# VM3300_V0_1.net
KiCad netlist of a schematic drawn in Altium Designer
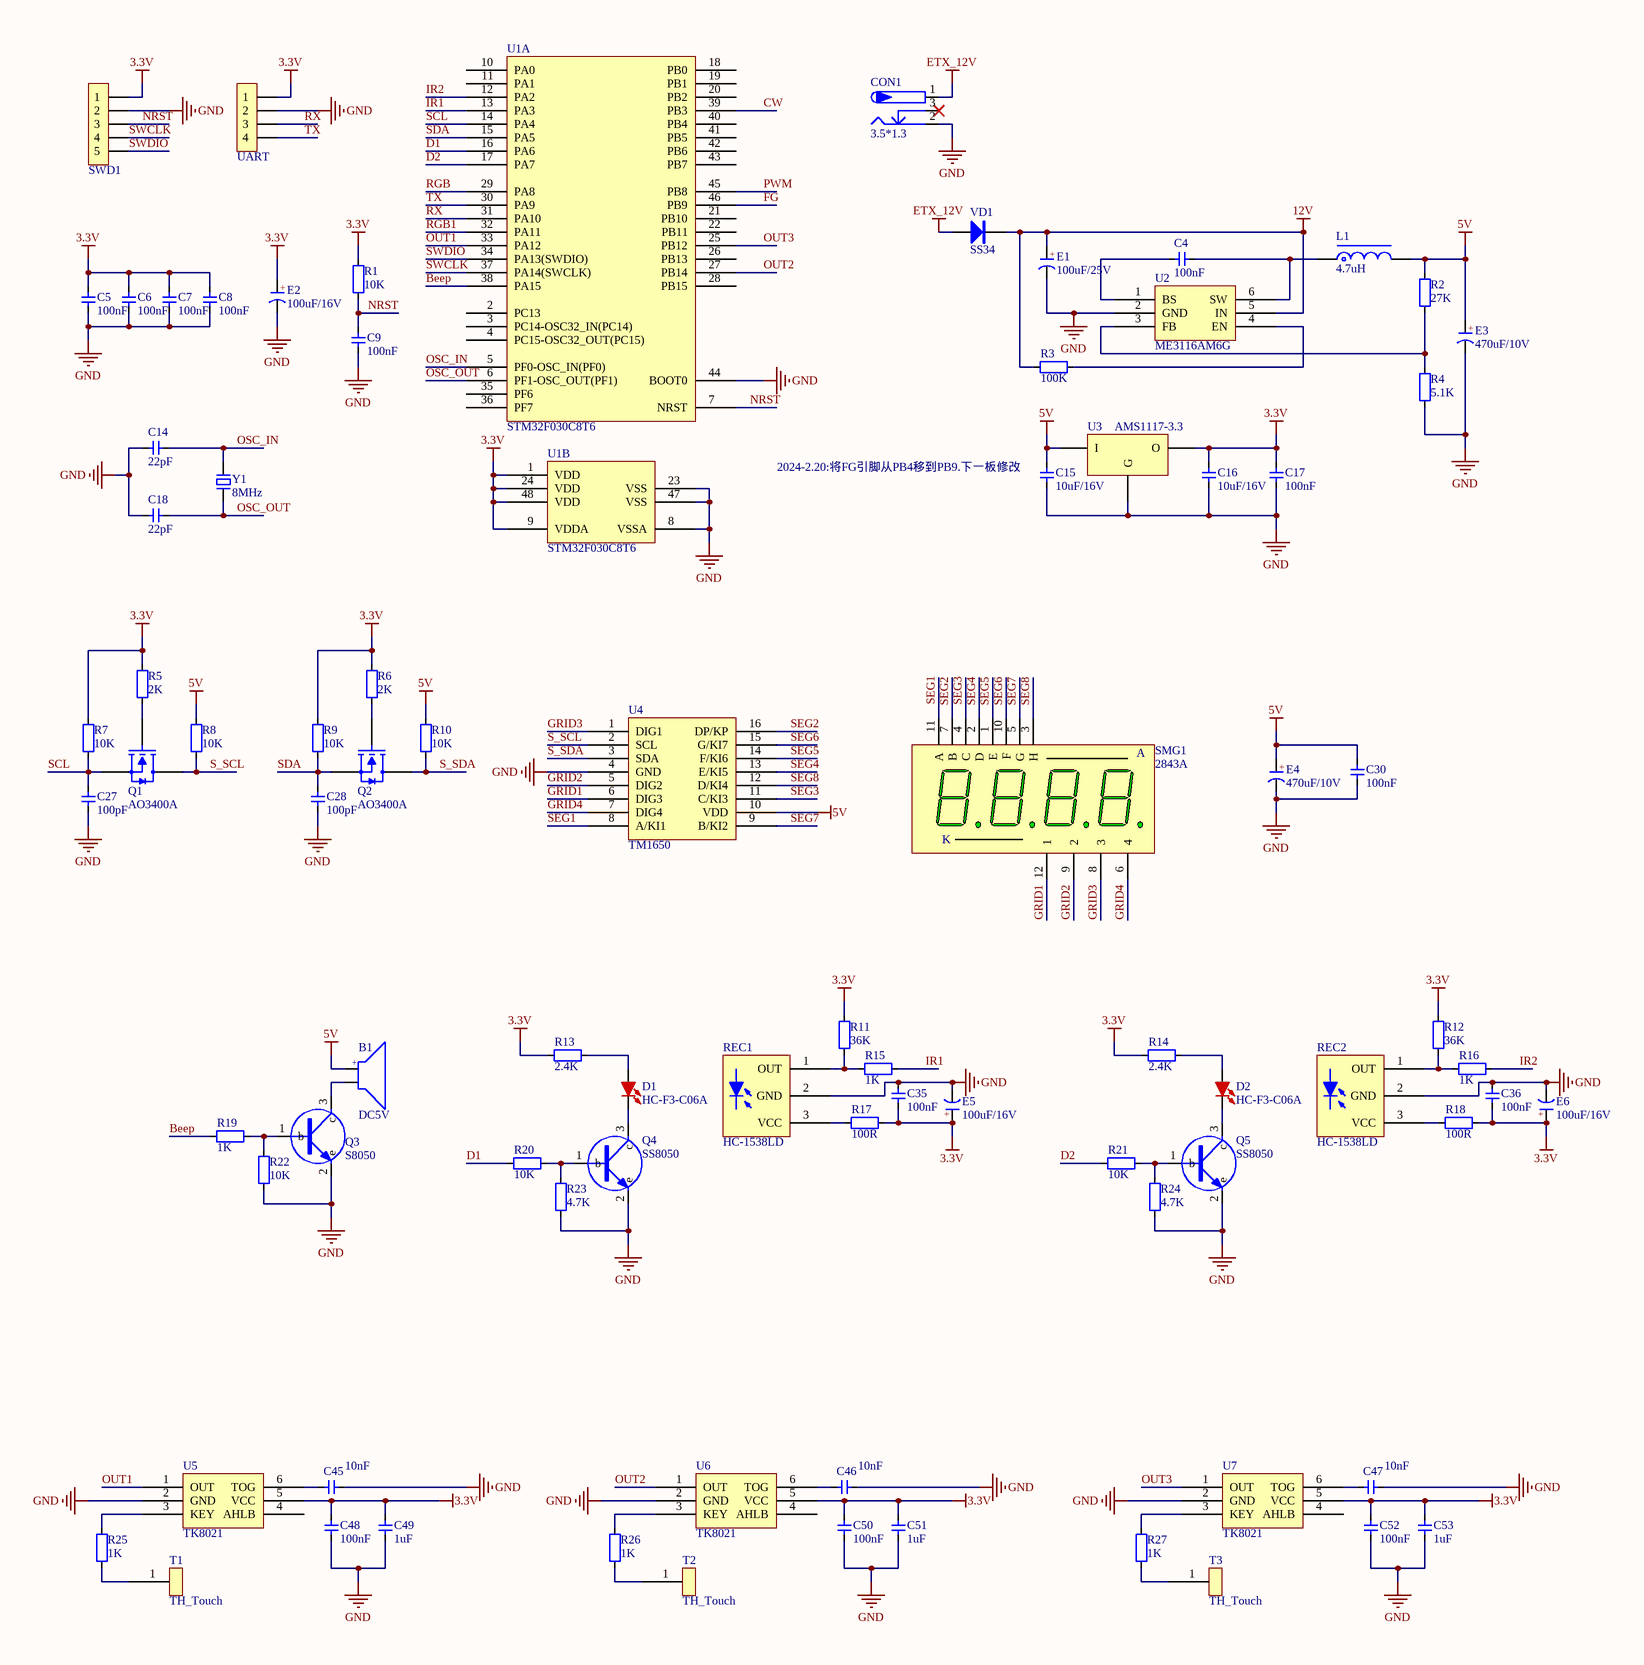
[diagram p0: VM3300_V0.1.SchDoc, left]
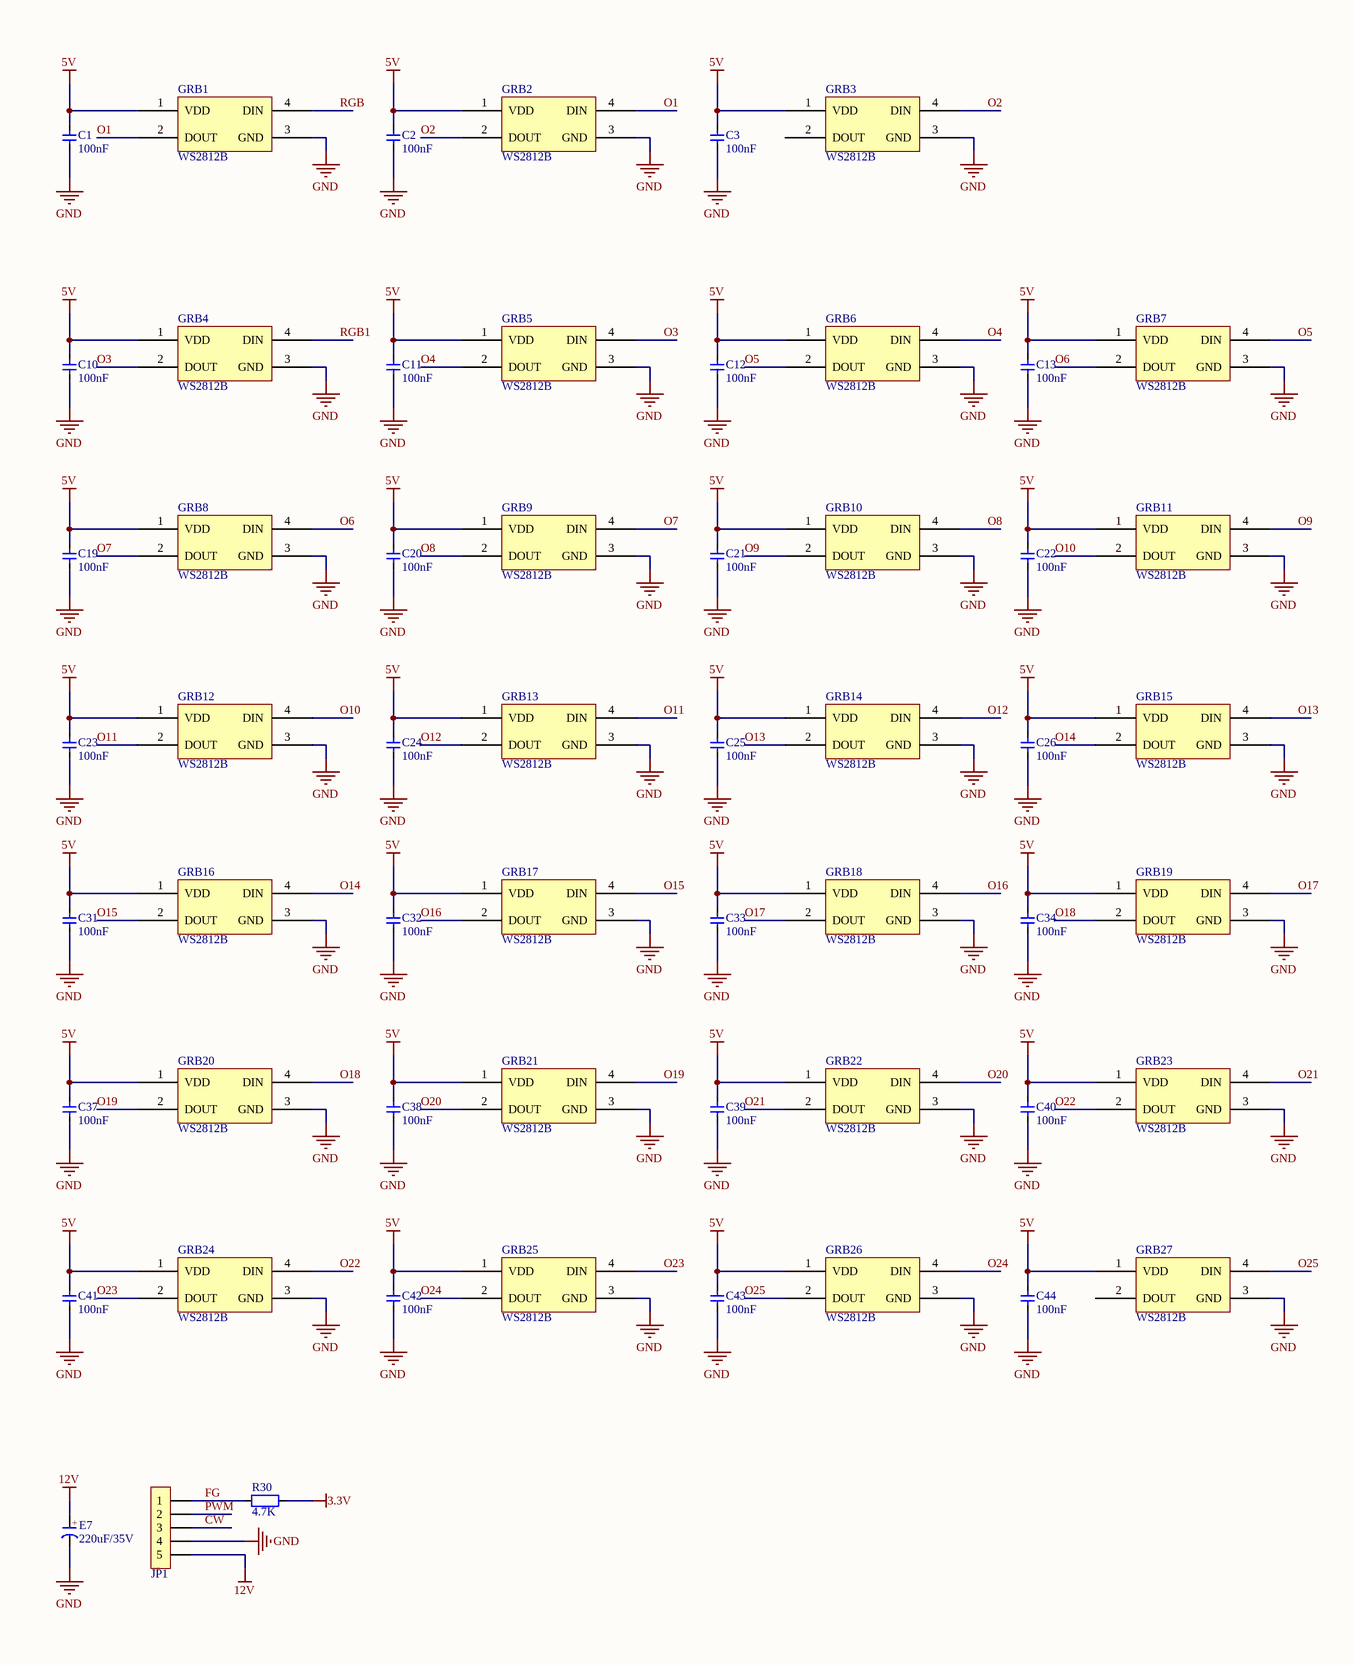
[diagram p1: VM3300_V0.1.SchDoc, right]

(export (version "E")
  (design (tool "Eeschema 10.0.6"))
  (components
    (comp (ref "B1")
      (value "DC5V")
      (footprint "BEEP 7.6x12x7.5")
      (description "蜂鸣器")
      (fields (field (name "版权归属") "源创客"))
      (libsource (lib "模块器件") (part "BEEP"))
    )
    (comp (ref "C1")
      (value "100nF")
      (footprint "C 0603")
      (description "无极性贴片电容")
      (fields (field (name "版权归属") "源创客"))
      (libsource (lib "电容") (part "C"))
    )
    (comp (ref "C2")
      (value "100nF")
      (footprint "C 0603")
      (description "无极性贴片电容")
      (fields (field (name "版权归属") "源创客"))
      (libsource (lib "电容") (part "C"))
    )
    (comp (ref "C3")
      (value "100nF")
      (footprint "C 0603")
      (description "无极性贴片电容")
      (fields (field (name "版权归属") "源创客"))
      (libsource (lib "电容") (part "C"))
    )
    (comp (ref "C4")
      (value "100nF")
      (footprint "C 0603")
      (description "无极性贴片电容")
      (fields (field (name "版权归属") "源创客"))
      (libsource (lib "电容") (part "C"))
    )
    (comp (ref "C5")
      (value "100nF")
      (footprint "C 0603")
      (description "无极性贴片电容")
      (fields (field (name "版权归属") "源创客"))
      (libsource (lib "电容") (part "C"))
    )
    (comp (ref "C6")
      (value "100nF")
      (footprint "C 0603")
      (description "无极性贴片电容")
      (fields (field (name "版权归属") "源创客"))
      (libsource (lib "电容") (part "C"))
    )
    (comp (ref "C7")
      (value "100nF")
      (footprint "C 0603")
      (description "无极性贴片电容")
      (fields (field (name "版权归属") "源创客"))
      (libsource (lib "电容") (part "C"))
    )
    (comp (ref "C8")
      (value "100nF")
      (footprint "C 0603")
      (description "无极性贴片电容")
      (fields (field (name "版权归属") "源创客"))
      (libsource (lib "电容") (part "C"))
    )
    (comp (ref "C9")
      (value "100nF")
      (footprint "C 0603")
      (description "无极性贴片电容")
      (fields (field (name "版权归属") "源创客"))
      (libsource (lib "电容") (part "C"))
    )
    (comp (ref "C10")
      (value "100nF")
      (footprint "C 0603")
      (description "无极性贴片电容")
      (fields (field (name "版权归属") "源创客"))
      (libsource (lib "电容") (part "C"))
    )
    (comp (ref "C11")
      (value "100nF")
      (footprint "C 0603")
      (description "无极性贴片电容")
      (fields (field (name "版权归属") "源创客"))
      (libsource (lib "电容") (part "C"))
    )
    (comp (ref "C12")
      (value "100nF")
      (footprint "C 0603")
      (description "无极性贴片电容")
      (fields (field (name "版权归属") "源创客"))
      (libsource (lib "电容") (part "C"))
    )
    (comp (ref "C13")
      (value "100nF")
      (footprint "C 0603")
      (description "无极性贴片电容")
      (fields (field (name "版权归属") "源创客"))
      (libsource (lib "电容") (part "C"))
    )
    (comp (ref "C14")
      (value "22pF")
      (footprint "C 0603")
      (description "无极性贴片电容")
      (fields (field (name "版权归属") "源创客"))
      (libsource (lib "电容") (part "C"))
    )
    (comp (ref "C15")
      (value "10uF/16V")
      (footprint "C 0805")
      (description "无极性贴片电容")
      (fields (field (name "版权归属") "源创客"))
      (libsource (lib "电容") (part "C"))
    )
    (comp (ref "C16")
      (value "10uF/16V")
      (footprint "C 0805")
      (description "无极性贴片电容")
      (fields (field (name "版权归属") "源创客"))
      (libsource (lib "电容") (part "C"))
    )
    (comp (ref "C17")
      (value "100nF")
      (footprint "C 0603")
      (description "无极性贴片电容")
      (fields (field (name "版权归属") "源创客"))
      (libsource (lib "电容") (part "C"))
    )
    (comp (ref "C18")
      (value "22pF")
      (footprint "C 0603")
      (description "无极性贴片电容")
      (fields (field (name "版权归属") "源创客"))
      (libsource (lib "电容") (part "C"))
    )
    (comp (ref "C19")
      (value "100nF")
      (footprint "C 0603")
      (description "无极性贴片电容")
      (fields (field (name "版权归属") "源创客"))
      (libsource (lib "电容") (part "C"))
    )
    (comp (ref "C20")
      (value "100nF")
      (footprint "C 0603")
      (description "无极性贴片电容")
      (fields (field (name "版权归属") "源创客"))
      (libsource (lib "电容") (part "C"))
    )
    (comp (ref "C21")
      (value "100nF")
      (footprint "C 0603")
      (description "无极性贴片电容")
      (fields (field (name "版权归属") "源创客"))
      (libsource (lib "电容") (part "C"))
    )
    (comp (ref "C22")
      (value "100nF")
      (footprint "C 0603")
      (description "无极性贴片电容")
      (fields (field (name "版权归属") "源创客"))
      (libsource (lib "电容") (part "C"))
    )
    (comp (ref "C23")
      (value "100nF")
      (footprint "C 0603")
      (description "无极性贴片电容")
      (fields (field (name "版权归属") "源创客"))
      (libsource (lib "电容") (part "C"))
    )
    (comp (ref "C24")
      (value "100nF")
      (footprint "C 0603")
      (description "无极性贴片电容")
      (fields (field (name "版权归属") "源创客"))
      (libsource (lib "电容") (part "C"))
    )
    (comp (ref "C25")
      (value "100nF")
      (footprint "C 0603")
      (description "无极性贴片电容")
      (fields (field (name "版权归属") "源创客"))
      (libsource (lib "电容") (part "C"))
    )
    (comp (ref "C26")
      (value "100nF")
      (footprint "C 0603")
      (description "无极性贴片电容")
      (fields (field (name "版权归属") "源创客"))
      (libsource (lib "电容") (part "C"))
    )
    (comp (ref "C27")
      (value "100pF")
      (footprint "C 0603")
      (description "无极性贴片电容")
      (fields (field (name "版权归属") "源创客"))
      (libsource (lib "电容") (part "C"))
    )
    (comp (ref "C28")
      (value "100pF")
      (footprint "C 0603")
      (description "无极性贴片电容")
      (fields (field (name "版权归属") "源创客"))
      (libsource (lib "电容") (part "C"))
    )
    (comp (ref "C30")
      (value "100nF")
      (footprint "C 0603")
      (description "无极性贴片电容")
      (fields (field (name "版权归属") "源创客"))
      (libsource (lib "电容") (part "C"))
    )
    (comp (ref "C31")
      (value "100nF")
      (footprint "C 0603")
      (description "无极性贴片电容")
      (fields (field (name "版权归属") "源创客"))
      (libsource (lib "电容") (part "C"))
    )
    (comp (ref "C32")
      (value "100nF")
      (footprint "C 0603")
      (description "无极性贴片电容")
      (fields (field (name "版权归属") "源创客"))
      (libsource (lib "电容") (part "C"))
    )
    (comp (ref "C33")
      (value "100nF")
      (footprint "C 0603")
      (description "无极性贴片电容")
      (fields (field (name "版权归属") "源创客"))
      (libsource (lib "电容") (part "C"))
    )
    (comp (ref "C34")
      (value "100nF")
      (footprint "C 0603")
      (description "无极性贴片电容")
      (fields (field (name "版权归属") "源创客"))
      (libsource (lib "电容") (part "C"))
    )
    (comp (ref "C35")
      (value "100nF")
      (footprint "C 0603")
      (description "无极性贴片电容")
      (fields (field (name "版权归属") "源创客"))
      (libsource (lib "电容") (part "C"))
    )
    (comp (ref "C36")
      (value "100nF")
      (footprint "C 0603")
      (description "无极性贴片电容")
      (fields (field (name "版权归属") "源创客"))
      (libsource (lib "电容") (part "C"))
    )
    (comp (ref "C37")
      (value "100nF")
      (footprint "C 0603")
      (description "无极性贴片电容")
      (fields (field (name "版权归属") "源创客"))
      (libsource (lib "电容") (part "C"))
    )
    (comp (ref "C38")
      (value "100nF")
      (footprint "C 0603")
      (description "无极性贴片电容")
      (fields (field (name "版权归属") "源创客"))
      (libsource (lib "电容") (part "C"))
    )
    (comp (ref "C39")
      (value "100nF")
      (footprint "C 0603")
      (description "无极性贴片电容")
      (fields (field (name "版权归属") "源创客"))
      (libsource (lib "电容") (part "C"))
    )
    (comp (ref "C40")
      (value "100nF")
      (footprint "C 0603")
      (description "无极性贴片电容")
      (fields (field (name "版权归属") "源创客"))
      (libsource (lib "电容") (part "C"))
    )
    (comp (ref "C41")
      (value "100nF")
      (footprint "C 0603")
      (description "无极性贴片电容")
      (fields (field (name "版权归属") "源创客"))
      (libsource (lib "电容") (part "C"))
    )
    (comp (ref "C42")
      (value "100nF")
      (footprint "C 0603")
      (description "无极性贴片电容")
      (fields (field (name "版权归属") "源创客"))
      (libsource (lib "电容") (part "C"))
    )
    (comp (ref "C43")
      (value "100nF")
      (footprint "C 0603")
      (description "无极性贴片电容")
      (fields (field (name "版权归属") "源创客"))
      (libsource (lib "电容") (part "C"))
    )
    (comp (ref "C44")
      (value "100nF")
      (footprint "C 0603")
      (description "无极性贴片电容")
      (fields (field (name "版权归属") "源创客"))
      (libsource (lib "电容") (part "C"))
    )
    (comp (ref "C45")
      (value "10nF")
      (footprint "C 0603")
      (description "无极性贴片电容")
      (fields (field (name "版权归属") "源创客"))
      (libsource (lib "电容") (part "C"))
    )
    (comp (ref "C46")
      (value "10nF")
      (footprint "C 0603")
      (description "无极性贴片电容")
      (fields (field (name "版权归属") "源创客"))
      (libsource (lib "电容") (part "C"))
    )
    (comp (ref "C47")
      (value "10nF")
      (footprint "C 0603")
      (description "无极性贴片电容")
      (fields (field (name "版权归属") "源创客"))
      (libsource (lib "电容") (part "C"))
    )
    (comp (ref "C48")
      (value "100nF")
      (footprint "C 0603")
      (description "无极性贴片电容")
      (fields (field (name "版权归属") "源创客"))
      (libsource (lib "电容") (part "C"))
    )
    (comp (ref "C49")
      (value "1uF")
      (footprint "C 0603")
      (description "无极性贴片电容")
      (fields (field (name "版权归属") "源创客"))
      (libsource (lib "电容") (part "C"))
    )
    (comp (ref "C50")
      (value "100nF")
      (footprint "C 0603")
      (description "无极性贴片电容")
      (fields (field (name "版权归属") "源创客"))
      (libsource (lib "电容") (part "C"))
    )
    (comp (ref "C51")
      (value "1uF")
      (footprint "C 0603")
      (description "无极性贴片电容")
      (fields (field (name "版权归属") "源创客"))
      (libsource (lib "电容") (part "C"))
    )
    (comp (ref "C52")
      (value "100nF")
      (footprint "C 0603")
      (description "无极性贴片电容")
      (fields (field (name "版权归属") "源创客"))
      (libsource (lib "电容") (part "C"))
    )
    (comp (ref "C53")
      (value "1uF")
      (footprint "C 0603")
      (description "无极性贴片电容")
      (fields (field (name "版权归属") "源创客"))
      (libsource (lib "电容") (part "C"))
    )
    (comp (ref "CON1")
      (value "3.5*1.3")
      (footprint "DC-005")
      (description "低压电源接口")
      (fields (field (name "版权归属") "源创客"))
      (libsource (lib "接口类") (part "P-DC"))
    )
    (comp (ref "D1")
      (value "HC-F3-C06A")
      (footprint "HC-F3-C06A")
      (description "红外发射管")
      (libsource (lib "传感器") (part "HC-F3-C06A"))
    )
    (comp (ref "D2")
      (value "HC-F3-C06A")
      (footprint "HC-F3-C06A")
      (description "红外发射管")
      (libsource (lib "传感器") (part "HC-F3-C06A"))
    )
    (comp (ref "E1")
      (value "100uF/25V")
      (footprint "CAP 2.0*5*11 - BK")
      (description "直插电解电容")
      (fields (field (name "版权归属") "源创客"))
      (libsource (lib "电容") (part "C-CAP"))
    )
    (comp (ref "E2")
      (value "100uF/16V")
      (footprint "CAP 2.0*5*11 - BK")
      (description "直插电解电容")
      (fields (field (name "版权归属") "源创客"))
      (libsource (lib "电容") (part "C-CAP"))
    )
    (comp (ref "E3")
      (value "470uF/10V")
      (footprint "CAP 2.5*6.3*11.2 - BK")
      (description "直插电解电容")
      (fields (field (name "版权归属") "源创客"))
      (libsource (lib "电容") (part "C-CAP"))
    )
    (comp (ref "E4")
      (value "470uF/10V")
      (footprint "CAP 2.5*6.3*11.2 - BK")
      (description "直插电解电容")
      (fields (field (name "版权归属") "源创客"))
      (libsource (lib "电容") (part "C-CAP"))
    )
    (comp (ref "E5")
      (value "100uF/16V")
      (footprint "CAP 2.0*5*11 - BK")
      (description "直插电解电容")
      (fields (field (name "版权归属") "源创客"))
      (libsource (lib "电容") (part "C-CAP"))
    )
    (comp (ref "E6")
      (value "100uF/16V")
      (footprint "CAP 2.0*5*11 - BK")
      (description "直插电解电容")
      (fields (field (name "版权归属") "源创客"))
      (libsource (lib "电容") (part "C-CAP"))
    )
    (comp (ref "E7")
      (value "220uF/35V")
      (footprint "CAP 3.5*8*11.5 - BK")
      (description "直插电解电容")
      (fields (field (name "版权归属") "源创客"))
      (libsource (lib "电容") (part "C-CAP"))
    )
    (comp (ref "GRB1") (value "WS2812B") (footprint "WS2812B-3528") (libsource (lib "LED") (part "WS2812B")))
    (comp (ref "GRB2") (value "WS2812B") (footprint "WS2812B-3528") (libsource (lib "LED") (part "WS2812B")))
    (comp (ref "GRB3") (value "WS2812B") (footprint "WS2812B-3528") (libsource (lib "LED") (part "WS2812B")))
    (comp (ref "GRB4") (value "WS2812B") (footprint "WS2812B-3528") (libsource (lib "LED") (part "WS2812B")))
    (comp (ref "GRB5") (value "WS2812B") (footprint "WS2812B-3528") (libsource (lib "LED") (part "WS2812B")))
    (comp (ref "GRB6") (value "WS2812B") (footprint "WS2812B-3528") (libsource (lib "LED") (part "WS2812B")))
    (comp (ref "GRB7") (value "WS2812B") (footprint "WS2812B-3528") (libsource (lib "LED") (part "WS2812B")))
    (comp (ref "GRB8") (value "WS2812B") (footprint "WS2812B-3528") (libsource (lib "LED") (part "WS2812B")))
    (comp (ref "GRB9") (value "WS2812B") (footprint "WS2812B-3528") (libsource (lib "LED") (part "WS2812B")))
    (comp (ref "GRB10") (value "WS2812B") (footprint "WS2812B-3528") (libsource (lib "LED") (part "WS2812B")))
    (comp (ref "GRB11") (value "WS2812B") (footprint "WS2812B-3528") (libsource (lib "LED") (part "WS2812B")))
    (comp (ref "GRB12") (value "WS2812B") (footprint "WS2812B-3528") (libsource (lib "LED") (part "WS2812B")))
    (comp (ref "GRB13") (value "WS2812B") (footprint "WS2812B-3528") (libsource (lib "LED") (part "WS2812B")))
    (comp (ref "GRB14") (value "WS2812B") (footprint "WS2812B-3528") (libsource (lib "LED") (part "WS2812B")))
    (comp (ref "GRB15") (value "WS2812B") (footprint "WS2812B-3528") (libsource (lib "LED") (part "WS2812B")))
    (comp (ref "GRB16") (value "WS2812B") (footprint "WS2812B-3528") (libsource (lib "LED") (part "WS2812B")))
    (comp (ref "GRB17") (value "WS2812B") (footprint "WS2812B-3528") (libsource (lib "LED") (part "WS2812B")))
    (comp (ref "GRB18") (value "WS2812B") (footprint "WS2812B-3528") (libsource (lib "LED") (part "WS2812B")))
    (comp (ref "GRB19") (value "WS2812B") (footprint "WS2812B-3528") (libsource (lib "LED") (part "WS2812B")))
    (comp (ref "GRB20") (value "WS2812B") (footprint "WS2812B-3528") (libsource (lib "LED") (part "WS2812B")))
    (comp (ref "GRB21") (value "WS2812B") (footprint "WS2812B-3528") (libsource (lib "LED") (part "WS2812B")))
    (comp (ref "GRB22") (value "WS2812B") (footprint "WS2812B-3528") (libsource (lib "LED") (part "WS2812B")))
    (comp (ref "GRB23") (value "WS2812B") (footprint "WS2812B-3528") (libsource (lib "LED") (part "WS2812B")))
    (comp (ref "GRB24") (value "WS2812B") (footprint "WS2812B-3528") (libsource (lib "LED") (part "WS2812B")))
    (comp (ref "GRB25") (value "WS2812B") (footprint "WS2812B-3528") (libsource (lib "LED") (part "WS2812B")))
    (comp (ref "GRB26") (value "WS2812B") (footprint "WS2812B-3528") (libsource (lib "LED") (part "WS2812B")))
    (comp (ref "GRB27") (value "WS2812B") (footprint "WS2812B-3528") (libsource (lib "LED") (part "WS2812B")))
    (comp (ref "JP1")
      (value "HDR-1X5")
      (footprint "XH2.54-5P")
      (description "5P接插件")
      (fields (field (name "版权归属") "源创客"))
      (libsource (lib "排针-排母") (part "Header 5"))
    )
    (comp (ref "L1")
      (value "4.7uH")
      (footprint "CD32")
      (description "贴片功率电感")
      (fields (field (name "版权归属") "源创客"))
      (libsource (lib "电感") (part "L-CD"))
    )
    (comp (ref "Q1")
      (value "AO3400A")
      (footprint "SOT23-3")
      (description "N-MOS")
      (libsource (lib "三极管") (part "AO3400A"))
    )
    (comp (ref "Q2")
      (value "AO3400A")
      (footprint "SOT23-3")
      (description "N-MOS")
      (libsource (lib "三极管") (part "AO3400A"))
    )
    (comp (ref "Q3") (value "S8050") (footprint "SOT23-3L") (libsource (lib "三极管") (part "NPN")))
    (comp (ref "Q4") (value "SS8050") (footprint "SOT23-3L") (libsource (lib "三极管") (part "NPN")))
    (comp (ref "Q5") (value "SS8050") (footprint "SOT23-3L") (libsource (lib "三极管") (part "NPN")))
    (comp (ref "R1")
      (value "10K")
      (footprint "R 0603")
      (description "贴片电阻")
      (fields (field (name "版权归属") "源创客"))
      (libsource (lib "") (part "R_1"))
    )
    (comp (ref "R2")
      (value "27K")
      (footprint "R 0603")
      (description "贴片电阻")
      (fields (field (name "版权归属") "源创客"))
      (libsource (lib "") (part "R_1"))
    )
    (comp (ref "R3")
      (value "100K")
      (footprint "R 0603")
      (description "贴片电阻")
      (fields (field (name "版权归属") "源创客"))
      (libsource (lib "电阻") (part "R"))
    )
    (comp (ref "R4")
      (value "5.1K")
      (footprint "R 0603")
      (description "贴片电阻")
      (fields (field (name "版权归属") "源创客"))
      (libsource (lib "") (part "R_1"))
    )
    (comp (ref "R5")
      (value "2K")
      (footprint "R 0603")
      (description "贴片电阻")
      (fields (field (name "版权归属") "源创客"))
      (libsource (lib "") (part "R_1"))
    )
    (comp (ref "R6")
      (value "2K")
      (footprint "R 0603")
      (description "贴片电阻")
      (fields (field (name "版权归属") "源创客"))
      (libsource (lib "") (part "R_1"))
    )
    (comp (ref "R7")
      (value "10K")
      (footprint "R 0603")
      (description "贴片电阻")
      (fields (field (name "版权归属") "源创客"))
      (libsource (lib "") (part "R_1"))
    )
    (comp (ref "R8")
      (value "10K")
      (footprint "R 0603")
      (description "贴片电阻")
      (fields (field (name "版权归属") "源创客"))
      (libsource (lib "") (part "R_1"))
    )
    (comp (ref "R9")
      (value "10K")
      (footprint "R 0603")
      (description "贴片电阻")
      (fields (field (name "版权归属") "源创客"))
      (libsource (lib "") (part "R_1"))
    )
    (comp (ref "R10")
      (value "10K")
      (footprint "R 0603")
      (description "贴片电阻")
      (fields (field (name "版权归属") "源创客"))
      (libsource (lib "") (part "R_1"))
    )
    (comp (ref "R11")
      (value "36K")
      (footprint "R 0603")
      (description "贴片电阻")
      (fields (field (name "版权归属") "源创客"))
      (libsource (lib "") (part "R_1"))
    )
    (comp (ref "R12")
      (value "36K")
      (footprint "R 0603")
      (description "贴片电阻")
      (fields (field (name "版权归属") "源创客"))
      (libsource (lib "") (part "R_1"))
    )
    (comp (ref "R13")
      (value "2.4K")
      (footprint "R 0603")
      (description "贴片电阻")
      (fields (field (name "版权归属") "源创客"))
      (libsource (lib "电阻") (part "R"))
    )
    (comp (ref "R14")
      (value "2.4K")
      (footprint "R 0603")
      (description "贴片电阻")
      (fields (field (name "版权归属") "源创客"))
      (libsource (lib "电阻") (part "R"))
    )
    (comp (ref "R15")
      (value "1K")
      (footprint "R 0603")
      (description "贴片电阻")
      (fields (field (name "版权归属") "源创客"))
      (libsource (lib "电阻") (part "R"))
    )
    (comp (ref "R16")
      (value "1K")
      (footprint "R 0603")
      (description "贴片电阻")
      (fields (field (name "版权归属") "源创客"))
      (libsource (lib "电阻") (part "R"))
    )
    (comp (ref "R17")
      (value "100R")
      (footprint "R 0603")
      (description "贴片电阻")
      (fields (field (name "版权归属") "源创客"))
      (libsource (lib "电阻") (part "R"))
    )
    (comp (ref "R18")
      (value "100R")
      (footprint "R 0603")
      (description "贴片电阻")
      (fields (field (name "版权归属") "源创客"))
      (libsource (lib "电阻") (part "R"))
    )
    (comp (ref "R19")
      (value "1K")
      (footprint "R 0603")
      (description "贴片电阻")
      (fields (field (name "版权归属") "源创客"))
      (libsource (lib "电阻") (part "R"))
    )
    (comp (ref "R20")
      (value "10K")
      (footprint "R 0603")
      (description "贴片电阻")
      (fields (field (name "版权归属") "源创客"))
      (libsource (lib "电阻") (part "R"))
    )
    (comp (ref "R21")
      (value "10K")
      (footprint "R 0603")
      (description "贴片电阻")
      (fields (field (name "版权归属") "源创客"))
      (libsource (lib "电阻") (part "R"))
    )
    (comp (ref "R22")
      (value "10K")
      (footprint "R 0603")
      (description "贴片电阻")
      (fields (field (name "版权归属") "源创客"))
      (libsource (lib "") (part "R_1"))
    )
    (comp (ref "R23")
      (value "4.7K")
      (footprint "R 0603")
      (description "贴片电阻")
      (fields (field (name "版权归属") "源创客"))
      (libsource (lib "") (part "R_1"))
    )
    (comp (ref "R24")
      (value "4.7K")
      (footprint "R 0603")
      (description "贴片电阻")
      (fields (field (name "版权归属") "源创客"))
      (libsource (lib "") (part "R_1"))
    )
    (comp (ref "R25")
      (value "1K")
      (footprint "R 0603")
      (description "贴片电阻")
      (fields (field (name "版权归属") "源创客"))
      (libsource (lib "") (part "R_1"))
    )
    (comp (ref "R26")
      (value "1K")
      (footprint "R 0603")
      (description "贴片电阻")
      (fields (field (name "版权归属") "源创客"))
      (libsource (lib "") (part "R_1"))
    )
    (comp (ref "R27")
      (value "1K")
      (footprint "R 0603")
      (description "贴片电阻")
      (fields (field (name "版权归属") "源创客"))
      (libsource (lib "") (part "R_1"))
    )
    (comp (ref "R30")
      (value "4.7K")
      (footprint "R 0603")
      (description "贴片电阻")
      (fields (field (name "版权归属") "源创客"))
      (libsource (lib "电阻") (part "R"))
    )
    (comp (ref "REC1")
      (value "HC-1538LD")
      (footprint "HC-1538LD-W")
      (description "红外接收管")
      (libsource (lib "传感器") (part "HC-1538LD"))
    )
    (comp (ref "REC2")
      (value "HC-1538LD")
      (footprint "HC-1538LD-W")
      (description "红外接收管")
      (libsource (lib "传感器") (part "HC-1538LD"))
    )
    (comp (ref "SMG1")
      (value "2843A")
      (footprint "SMG 0.28_4P_JOANLAB")
      (description "JOANLAB-0.28寸4位共阴数码管")
      (fields (field (name "版权归属") "源创客"))
      (libsource (lib "显示器件") (part "2843A"))
    )
    (comp (ref "SWD1")
      (value "HDR-1X5")
      (footprint "SWD_JOANLAB")
      (description "5P接插件")
      (fields (field (name "版权归属") "源创客"))
      (libsource (lib "排针-排母") (part "Header 5"))
    )
    (comp (ref "T1")
      (value "TH_Touch")
      (footprint "TH_Touch")
      (description "触摸弹簧，用于触摸感应")
      (libsource (lib "模块器件") (part "TH_Touch"))
    )
    (comp (ref "T2")
      (value "TH_Touch")
      (footprint "TH_Touch")
      (description "触摸弹簧，用于触摸感应")
      (libsource (lib "模块器件") (part "TH_Touch"))
    )
    (comp (ref "T3")
      (value "TH_Touch")
      (footprint "TH_Touch")
      (description "触摸弹簧，用于触摸感应")
      (libsource (lib "模块器件") (part "TH_Touch"))
    )
    (comp (ref "U1")
      (value "STM32F030C8T6")
      (footprint "STM32F030C8T6")
      (libsource (lib "STM32系列单片机") (part "STM32F030C8T6"))
    )
    (comp (ref "U2")
      (value "ME3116AM6G")
      (footprint "ME3116AM6G")
      (description "DC-DC电源芯片  24-40V->5V")
      (libsource (lib "变压器") (part "ME3116AM6G"))
    )
    (comp (ref "U3")
      (value "AMS1117-3.3")
      (footprint "AMS1117-3.3")
      (description "转3.3V电压")
      (libsource (lib "变压器") (part "AMS1117-3.3"))
    )
    (comp (ref "U4")
      (value "TM1650")
      (footprint "TM1650")
      (description "TM1650是一种带键盘扫描接口的LED（发光二极管显示器）驱动控制专用IC,内部集成有MCU\r\n数字接口、数据锁存器、LED驱动、键盘扫描等电路。")
      (libsource (lib "显示芯片") (part "TM1650"))
    )
    (comp (ref "U5")
      (value "TK8021")
      (footprint "TK8021")
      (description "单通道自校正触摸感应芯片")
      (libsource (lib "常用芯片") (part "TTP2233"))
    )
    (comp (ref "U6")
      (value "TK8021")
      (footprint "TK8021")
      (description "单通道自校正触摸感应芯片")
      (libsource (lib "常用芯片") (part "TTP2233"))
    )
    (comp (ref "U7")
      (value "TK8021")
      (footprint "TK8021")
      (description "单通道自校正触摸感应芯片")
      (libsource (lib "常用芯片") (part "TTP2233"))
    )
    (comp (ref "UART")
      (value "HDR-1X4")
      (footprint "XH2.54-4P")
      (description "4P接插件")
      (fields (field (name "版权归属") "源创客"))
      (libsource (lib "排针-排母") (part "Header 4"))
    )
    (comp (ref "VD1")
      (value "SS34")
      (footprint "SMA")
      (description "肖特基二极管")
      (fields (field (name "版权归属") "源创客"))
      (libsource (lib "二极管-整流桥") (part "SS34"))
    )
    (comp (ref "Y1")
      (value "8MHz")
      (footprint "XTAL-49S SMD")
      (description "2脚晶振")
      (fields (field (name "版权归属") "源创客"))
      (libsource (lib "晶振") (part "XTAL-2"))
    )
  )
  (nets
    (net (code "1") (name "/Beep") (class "Default")
      (node (ref "R19") (pin "1") (pinfunction "1_1") (pintype "passive"))
      (node (ref "U1") (pin "38") (pinfunction "PA15_38") (pintype "passive"))
    )
    (net (code "2") (name "/CW") (class "Default")
      (node (ref "JP1") (pin "3") (pinfunction "3_3") (pintype "passive"))
      (node (ref "U1") (pin "39") (pinfunction "PB3_39") (pintype "passive"))
    )
    (net (code "3") (name "/D1") (class "Default")
      (node (ref "R20") (pin "1") (pinfunction "1_1") (pintype "passive"))
      (node (ref "U1") (pin "16") (pinfunction "PA6_16") (pintype "passive"))
    )
    (net (code "4") (name "/D2") (class "Default")
      (node (ref "R21") (pin "1") (pinfunction "1_1") (pintype "passive"))
      (node (ref "U1") (pin "17") (pinfunction "PA7_17") (pintype "passive"))
    )
    (net (code "5") (name "/FG") (class "Default")
      (node (ref "JP1") (pin "1") (pinfunction "1_1") (pintype "passive"))
      (node (ref "R30") (pin "1") (pinfunction "1_1") (pintype "passive"))
      (node (ref "U1") (pin "46") (pinfunction "PB9_46") (pintype "passive"))
    )
    (net (code "6") (name "/GRID1") (class "Default")
      (node (ref "SMG1") (pin "12") (pinfunction "1_12") (pintype "passive"))
      (node (ref "U4") (pin "6") (pinfunction "DIG3_6") (pintype "passive"))
    )
    (net (code "7") (name "/GRID2") (class "Default")
      (node (ref "SMG1") (pin "9") (pinfunction "2_9") (pintype "passive"))
      (node (ref "U4") (pin "5") (pinfunction "DIG2_5") (pintype "passive"))
    )
    (net (code "8") (name "/GRID3") (class "Default")
      (node (ref "SMG1") (pin "8") (pinfunction "3_8") (pintype "passive"))
      (node (ref "U4") (pin "1") (pinfunction "DIG1_1") (pintype "passive"))
    )
    (net (code "9") (name "/GRID4") (class "Default")
      (node (ref "SMG1") (pin "6") (pinfunction "4_6") (pintype "passive"))
      (node (ref "U4") (pin "7") (pinfunction "DIG4_7") (pintype "passive"))
    )
    (net (code "10") (name "/IR1") (class "Default")
      (node (ref "R15") (pin "2") (pinfunction "2_2") (pintype "passive"))
      (node (ref "U1") (pin "13") (pinfunction "PA3_13") (pintype "passive"))
    )
    (net (code "11") (name "/IR2") (class "Default")
      (node (ref "R16") (pin "2") (pinfunction "2_2") (pintype "passive"))
      (node (ref "U1") (pin "12") (pinfunction "PA2_12") (pintype "passive"))
    )
    (net (code "12") (name "/NRST") (class "Default")
      (node (ref "C9") (pin "2") (pinfunction "2_2") (pintype "passive"))
      (node (ref "R1") (pin "1") (pinfunction "1_1") (pintype "passive"))
      (node (ref "SWD1") (pin "3") (pinfunction "3_3") (pintype "passive"))
      (node (ref "U1") (pin "7") (pinfunction "NRST_7") (pintype "passive"))
    )
    (net (code "13") (name "/O1") (class "Default")
      (node (ref "GRB1") (pin "2") (pinfunction "DOUT_2") (pintype "passive"))
      (node (ref "GRB2") (pin "4") (pinfunction "DIN_4") (pintype "passive"))
    )
    (net (code "14") (name "/O2") (class "Default")
      (node (ref "GRB2") (pin "2") (pinfunction "DOUT_2") (pintype "passive"))
      (node (ref "GRB3") (pin "4") (pinfunction "DIN_4") (pintype "passive"))
    )
    (net (code "15") (name "/O3") (class "Default")
      (node (ref "GRB4") (pin "2") (pinfunction "DOUT_2") (pintype "passive"))
      (node (ref "GRB5") (pin "4") (pinfunction "DIN_4") (pintype "passive"))
    )
    (net (code "16") (name "/O4") (class "Default")
      (node (ref "GRB5") (pin "2") (pinfunction "DOUT_2") (pintype "passive"))
      (node (ref "GRB6") (pin "4") (pinfunction "DIN_4") (pintype "passive"))
    )
    (net (code "17") (name "/O5") (class "Default")
      (node (ref "GRB6") (pin "2") (pinfunction "DOUT_2") (pintype "passive"))
      (node (ref "GRB7") (pin "4") (pinfunction "DIN_4") (pintype "passive"))
    )
    (net (code "18") (name "/O6") (class "Default")
      (node (ref "GRB7") (pin "2") (pinfunction "DOUT_2") (pintype "passive"))
      (node (ref "GRB8") (pin "4") (pinfunction "DIN_4") (pintype "passive"))
    )
    (net (code "19") (name "/O7") (class "Default")
      (node (ref "GRB8") (pin "2") (pinfunction "DOUT_2") (pintype "passive"))
      (node (ref "GRB9") (pin "4") (pinfunction "DIN_4") (pintype "passive"))
    )
    (net (code "20") (name "/O8") (class "Default")
      (node (ref "GRB10") (pin "4") (pinfunction "DIN_4") (pintype "passive"))
      (node (ref "GRB9") (pin "2") (pinfunction "DOUT_2") (pintype "passive"))
    )
    (net (code "21") (name "/O9") (class "Default")
      (node (ref "GRB10") (pin "2") (pinfunction "DOUT_2") (pintype "passive"))
      (node (ref "GRB11") (pin "4") (pinfunction "DIN_4") (pintype "passive"))
    )
    (net (code "22") (name "/O10") (class "Default")
      (node (ref "GRB11") (pin "2") (pinfunction "DOUT_2") (pintype "passive"))
      (node (ref "GRB12") (pin "4") (pinfunction "DIN_4") (pintype "passive"))
    )
    (net (code "23") (name "/O11") (class "Default")
      (node (ref "GRB12") (pin "2") (pinfunction "DOUT_2") (pintype "passive"))
      (node (ref "GRB13") (pin "4") (pinfunction "DIN_4") (pintype "passive"))
    )
    (net (code "24") (name "/O12") (class "Default")
      (node (ref "GRB13") (pin "2") (pinfunction "DOUT_2") (pintype "passive"))
      (node (ref "GRB14") (pin "4") (pinfunction "DIN_4") (pintype "passive"))
    )
    (net (code "25") (name "/O13") (class "Default")
      (node (ref "GRB14") (pin "2") (pinfunction "DOUT_2") (pintype "passive"))
      (node (ref "GRB15") (pin "4") (pinfunction "DIN_4") (pintype "passive"))
    )
    (net (code "26") (name "/O14") (class "Default")
      (node (ref "GRB15") (pin "2") (pinfunction "DOUT_2") (pintype "passive"))
      (node (ref "GRB16") (pin "4") (pinfunction "DIN_4") (pintype "passive"))
    )
    (net (code "27") (name "/O15") (class "Default")
      (node (ref "GRB16") (pin "2") (pinfunction "DOUT_2") (pintype "passive"))
      (node (ref "GRB17") (pin "4") (pinfunction "DIN_4") (pintype "passive"))
    )
    (net (code "28") (name "/O16") (class "Default")
      (node (ref "GRB17") (pin "2") (pinfunction "DOUT_2") (pintype "passive"))
      (node (ref "GRB18") (pin "4") (pinfunction "DIN_4") (pintype "passive"))
    )
    (net (code "29") (name "/O17") (class "Default")
      (node (ref "GRB18") (pin "2") (pinfunction "DOUT_2") (pintype "passive"))
      (node (ref "GRB19") (pin "4") (pinfunction "DIN_4") (pintype "passive"))
    )
    (net (code "30") (name "/O18") (class "Default")
      (node (ref "GRB19") (pin "2") (pinfunction "DOUT_2") (pintype "passive"))
      (node (ref "GRB20") (pin "4") (pinfunction "DIN_4") (pintype "passive"))
    )
    (net (code "31") (name "/O19") (class "Default")
      (node (ref "GRB20") (pin "2") (pinfunction "DOUT_2") (pintype "passive"))
      (node (ref "GRB21") (pin "4") (pinfunction "DIN_4") (pintype "passive"))
    )
    (net (code "32") (name "/O20") (class "Default")
      (node (ref "GRB21") (pin "2") (pinfunction "DOUT_2") (pintype "passive"))
      (node (ref "GRB22") (pin "4") (pinfunction "DIN_4") (pintype "passive"))
    )
    (net (code "33") (name "/O21") (class "Default")
      (node (ref "GRB22") (pin "2") (pinfunction "DOUT_2") (pintype "passive"))
      (node (ref "GRB23") (pin "4") (pinfunction "DIN_4") (pintype "passive"))
    )
    (net (code "34") (name "/O22") (class "Default")
      (node (ref "GRB23") (pin "2") (pinfunction "DOUT_2") (pintype "passive"))
      (node (ref "GRB24") (pin "4") (pinfunction "DIN_4") (pintype "passive"))
    )
    (net (code "35") (name "/O23") (class "Default")
      (node (ref "GRB24") (pin "2") (pinfunction "DOUT_2") (pintype "passive"))
      (node (ref "GRB25") (pin "4") (pinfunction "DIN_4") (pintype "passive"))
    )
    (net (code "36") (name "/O24") (class "Default")
      (node (ref "GRB25") (pin "2") (pinfunction "DOUT_2") (pintype "passive"))
      (node (ref "GRB26") (pin "4") (pinfunction "DIN_4") (pintype "passive"))
    )
    (net (code "37") (name "/O25") (class "Default")
      (node (ref "GRB26") (pin "2") (pinfunction "DOUT_2") (pintype "passive"))
      (node (ref "GRB27") (pin "4") (pinfunction "DIN_4") (pintype "passive"))
    )
    (net (code "38") (name "/OSC_IN") (class "Default")
      (node (ref "C14") (pin "2") (pinfunction "2_2") (pintype "passive"))
      (node (ref "U1") (pin "5") (pinfunction "PF0-OSC_IN(PF0)_5") (pintype "passive"))
      (node (ref "Y1") (pin "2") (pinfunction "2_2") (pintype "passive"))
    )
    (net (code "39") (name "/OSC_OUT") (class "Default")
      (node (ref "C18") (pin "2") (pinfunction "2_2") (pintype "passive"))
      (node (ref "U1") (pin "6") (pinfunction "PF1-OSC_OUT(PF1)_6") (pintype "passive"))
      (node (ref "Y1") (pin "1") (pinfunction "1_1") (pintype "passive"))
    )
    (net (code "40") (name "/OUT1") (class "Default")
      (node (ref "U1") (pin "33") (pinfunction "PA12_33") (pintype "passive"))
      (node (ref "U5") (pin "1") (pinfunction "OUT_1") (pintype "passive"))
    )
    (net (code "41") (name "/OUT2") (class "Default")
      (node (ref "U1") (pin "27") (pinfunction "PB14_27") (pintype "passive"))
      (node (ref "U6") (pin "1") (pinfunction "OUT_1") (pintype "passive"))
    )
    (net (code "42") (name "/OUT3") (class "Default")
      (node (ref "U1") (pin "25") (pinfunction "PB12_25") (pintype "passive"))
      (node (ref "U7") (pin "1") (pinfunction "OUT_1") (pintype "passive"))
    )
    (net (code "43") (name "/PWM") (class "Default")
      (node (ref "JP1") (pin "2") (pinfunction "2_2") (pintype "passive"))
      (node (ref "U1") (pin "45") (pinfunction "PB8_45") (pintype "passive"))
    )
    (net (code "44") (name "/RGB") (class "Default")
      (node (ref "GRB1") (pin "4") (pinfunction "DIN_4") (pintype "passive"))
      (node (ref "U1") (pin "29") (pinfunction "PA8_29") (pintype "passive"))
    )
    (net (code "45") (name "/RGB1") (class "Default")
      (node (ref "GRB4") (pin "4") (pinfunction "DIN_4") (pintype "passive"))
      (node (ref "U1") (pin "32") (pinfunction "PA11_32") (pintype "passive"))
    )
    (net (code "46") (name "/RX") (class "Default")
      (node (ref "U1") (pin "31") (pinfunction "PA10_31") (pintype "passive"))
      (node (ref "UART") (pin "3") (pinfunction "3_3") (pintype "passive"))
    )
    (net (code "47") (name "/SCL") (class "Default")
      (node (ref "C27") (pin "2") (pinfunction "2_2") (pintype "passive"))
      (node (ref "Q1") (pin "3") (pinfunction "S_3") (pintype "passive"))
      (node (ref "R7") (pin "1") (pinfunction "1_1") (pintype "passive"))
      (node (ref "U1") (pin "14") (pinfunction "PA4_14") (pintype "passive"))
    )
    (net (code "48") (name "/SDA") (class "Default")
      (node (ref "C28") (pin "2") (pinfunction "2_2") (pintype "passive"))
      (node (ref "Q2") (pin "3") (pinfunction "S_3") (pintype "passive"))
      (node (ref "R9") (pin "1") (pinfunction "1_1") (pintype "passive"))
      (node (ref "U1") (pin "15") (pinfunction "PA5_15") (pintype "passive"))
    )
    (net (code "49") (name "/SEG1") (class "Default")
      (node (ref "SMG1") (pin "11") (pinfunction "A_11") (pintype "passive"))
      (node (ref "U4") (pin "8") (pinfunction "A/KI1_8") (pintype "passive"))
    )
    (net (code "50") (name "/SEG2") (class "Default")
      (node (ref "SMG1") (pin "7") (pinfunction "B_7") (pintype "passive"))
      (node (ref "U4") (pin "16") (pinfunction "DP/KP_16") (pintype "passive"))
    )
    (net (code "51") (name "/SEG3") (class "Default")
      (node (ref "SMG1") (pin "4") (pinfunction "C_4") (pintype "passive"))
      (node (ref "U4") (pin "11") (pinfunction "C/KI3_11") (pintype "passive"))
    )
    (net (code "52") (name "/SEG4") (class "Default")
      (node (ref "SMG1") (pin "2") (pinfunction "D_2") (pintype "passive"))
      (node (ref "U4") (pin "13") (pinfunction "E/KI5_13") (pintype "passive"))
    )
    (net (code "53") (name "/SEG5") (class "Default")
      (node (ref "SMG1") (pin "1") (pinfunction "E_1") (pintype "passive"))
      (node (ref "U4") (pin "14") (pinfunction "F/KI6_14") (pintype "passive"))
    )
    (net (code "54") (name "/SEG6") (class "Default")
      (node (ref "SMG1") (pin "10") (pinfunction "F_10") (pintype "passive"))
      (node (ref "U4") (pin "15") (pinfunction "G/KI7_15") (pintype "passive"))
    )
    (net (code "55") (name "/SEG7") (class "Default")
      (node (ref "SMG1") (pin "5") (pinfunction "G_5") (pintype "passive"))
      (node (ref "U4") (pin "9") (pinfunction "B/KI2_9") (pintype "passive"))
    )
    (net (code "56") (name "/SEG8") (class "Default")
      (node (ref "SMG1") (pin "3") (pinfunction "H_3") (pintype "passive"))
      (node (ref "U4") (pin "12") (pinfunction "D/KI4_12") (pintype "passive"))
    )
    (net (code "57") (name "/SWCLK") (class "Default")
      (node (ref "SWD1") (pin "4") (pinfunction "4_4") (pintype "passive"))
      (node (ref "U1") (pin "37") (pinfunction "PA14(SWCLK)_37") (pintype "passive"))
    )
    (net (code "58") (name "/SWDIO") (class "Default")
      (node (ref "SWD1") (pin "5") (pinfunction "5_5") (pintype "passive"))
      (node (ref "U1") (pin "34") (pinfunction "PA13(SWDIO)_34") (pintype "passive"))
    )
    (net (code "59") (name "/S_SCL") (class "Default")
      (node (ref "Q1") (pin "2") (pinfunction "D_2") (pintype "passive"))
      (node (ref "R8") (pin "1") (pinfunction "1_1") (pintype "passive"))
      (node (ref "U4") (pin "2") (pinfunction "SCL_2") (pintype "passive"))
    )
    (net (code "60") (name "/S_SDA") (class "Default")
      (node (ref "Q2") (pin "2") (pinfunction "D_2") (pintype "passive"))
      (node (ref "R10") (pin "1") (pinfunction "1_1") (pintype "passive"))
      (node (ref "U4") (pin "3") (pinfunction "SDA_3") (pintype "passive"))
    )
    (net (code "61") (name "/TX") (class "Default")
      (node (ref "U1") (pin "30") (pinfunction "PA9_30") (pintype "passive"))
      (node (ref "UART") (pin "4") (pinfunction "4_4") (pintype "passive"))
    )
    (net (code "62") (name "3.3V") (class "Default")
      (node (ref "C16") (pin "2") (pinfunction "2_2") (pintype "passive"))
      (node (ref "C17") (pin "2") (pinfunction "2_2") (pintype "passive"))
      (node (ref "C35") (pin "1") (pinfunction "1_1") (pintype "passive"))
      (node (ref "C36") (pin "1") (pinfunction "1_1") (pintype "passive"))
      (node (ref "C48") (pin "2") (pinfunction "2_2") (pintype "passive"))
      (node (ref "C49") (pin "2") (pinfunction "2_2") (pintype "passive"))
      (node (ref "C5") (pin "2") (pinfunction "2_2") (pintype "passive"))
      (node (ref "C50") (pin "2") (pinfunction "2_2") (pintype "passive"))
      (node (ref "C51") (pin "2") (pinfunction "2_2") (pintype "passive"))
      (node (ref "C52") (pin "2") (pinfunction "2_2") (pintype "passive"))
      (node (ref "C53") (pin "2") (pinfunction "2_2") (pintype "passive"))
      (node (ref "C6") (pin "2") (pinfunction "2_2") (pintype "passive"))
      (node (ref "C7") (pin "2") (pinfunction "2_2") (pintype "passive"))
      (node (ref "C8") (pin "2") (pinfunction "2_2") (pintype "passive"))
      (node (ref "E2") (pin "1") (pinfunction "A_1") (pintype "passive"))
      (node (ref "E5") (pin "1") (pinfunction "A_1") (pintype "passive"))
      (node (ref "E6") (pin "1") (pinfunction "A_1") (pintype "passive"))
      (node (ref "R1") (pin "2") (pinfunction "2_2") (pintype "passive"))
      (node (ref "R11") (pin "2") (pinfunction "2_2") (pintype "passive"))
      (node (ref "R12") (pin "2") (pinfunction "2_2") (pintype "passive"))
      (node (ref "R13") (pin "1") (pinfunction "1_1") (pintype "passive"))
      (node (ref "R14") (pin "1") (pinfunction "1_1") (pintype "passive"))
      (node (ref "R17") (pin "2") (pinfunction "2_2") (pintype "passive"))
      (node (ref "R18") (pin "2") (pinfunction "2_2") (pintype "passive"))
      (node (ref "R30") (pin "2") (pinfunction "2_2") (pintype "passive"))
      (node (ref "R5") (pin "2") (pinfunction "2_2") (pintype "passive"))
      (node (ref "R6") (pin "2") (pinfunction "2_2") (pintype "passive"))
      (node (ref "R7") (pin "2") (pinfunction "2_2") (pintype "passive"))
      (node (ref "R9") (pin "2") (pinfunction "2_2") (pintype "passive"))
      (node (ref "SWD1") (pin "1") (pinfunction "1_1") (pintype "passive"))
      (node (ref "U1") (pin "1") (pinfunction "VDD_1") (pintype "passive"))
      (node (ref "U1") (pin "24") (pinfunction "VDD_24") (pintype "passive"))
      (node (ref "U1") (pin "48") (pinfunction "VDD_48") (pintype "passive"))
      (node (ref "U1") (pin "9") (pinfunction "VDDA_9") (pintype "passive"))
      (node (ref "U3") (pin "2") (pinfunction "O_2") (pintype "passive"))
      (node (ref "U5") (pin "5") (pinfunction "VCC_5") (pintype "passive"))
      (node (ref "U6") (pin "5") (pinfunction "VCC_5") (pintype "passive"))
      (node (ref "U7") (pin "5") (pinfunction "VCC_5") (pintype "passive"))
      (node (ref "UART") (pin "1") (pinfunction "1_1") (pintype "passive"))
    )
    (net (code "63") (name "5V") (class "Default")
      (node (ref "B1") (pin "1") (pinfunction "1_1") (pintype "passive"))
      (node (ref "C1") (pin "2") (pinfunction "2_2") (pintype "passive"))
      (node (ref "C10") (pin "2") (pinfunction "2_2") (pintype "passive"))
      (node (ref "C11") (pin "2") (pinfunction "2_2") (pintype "passive"))
      (node (ref "C12") (pin "2") (pinfunction "2_2") (pintype "passive"))
      (node (ref "C13") (pin "2") (pinfunction "2_2") (pintype "passive"))
      (node (ref "C15") (pin "2") (pinfunction "2_2") (pintype "passive"))
      (node (ref "C19") (pin "2") (pinfunction "2_2") (pintype "passive"))
      (node (ref "C2") (pin "2") (pinfunction "2_2") (pintype "passive"))
      (node (ref "C20") (pin "2") (pinfunction "2_2") (pintype "passive"))
      (node (ref "C21") (pin "2") (pinfunction "2_2") (pintype "passive"))
      (node (ref "C22") (pin "2") (pinfunction "2_2") (pintype "passive"))
      (node (ref "C23") (pin "2") (pinfunction "2_2") (pintype "passive"))
      (node (ref "C24") (pin "2") (pinfunction "2_2") (pintype "passive"))
      (node (ref "C25") (pin "2") (pinfunction "2_2") (pintype "passive"))
      (node (ref "C26") (pin "2") (pinfunction "2_2") (pintype "passive"))
      (node (ref "C3") (pin "2") (pinfunction "2_2") (pintype "passive"))
      (node (ref "C30") (pin "2") (pinfunction "2_2") (pintype "passive"))
      (node (ref "C31") (pin "2") (pinfunction "2_2") (pintype "passive"))
      (node (ref "C32") (pin "2") (pinfunction "2_2") (pintype "passive"))
      (node (ref "C33") (pin "2") (pinfunction "2_2") (pintype "passive"))
      (node (ref "C34") (pin "2") (pinfunction "2_2") (pintype "passive"))
      (node (ref "C37") (pin "2") (pinfunction "2_2") (pintype "passive"))
      (node (ref "C38") (pin "2") (pinfunction "2_2") (pintype "passive"))
      (node (ref "C39") (pin "2") (pinfunction "2_2") (pintype "passive"))
      (node (ref "C40") (pin "2") (pinfunction "2_2") (pintype "passive"))
      (node (ref "C41") (pin "2") (pinfunction "2_2") (pintype "passive"))
      (node (ref "C42") (pin "2") (pinfunction "2_2") (pintype "passive"))
      (node (ref "C43") (pin "2") (pinfunction "2_2") (pintype "passive"))
      (node (ref "C44") (pin "2") (pinfunction "2_2") (pintype "passive"))
      (node (ref "E3") (pin "1") (pinfunction "A_1") (pintype "passive"))
      (node (ref "E4") (pin "1") (pinfunction "A_1") (pintype "passive"))
      (node (ref "GRB1") (pin "1") (pinfunction "VDD_1") (pintype "passive"))
      (node (ref "GRB10") (pin "1") (pinfunction "VDD_1") (pintype "passive"))
      (node (ref "GRB11") (pin "1") (pinfunction "VDD_1") (pintype "passive"))
      (node (ref "GRB12") (pin "1") (pinfunction "VDD_1") (pintype "passive"))
      (node (ref "GRB13") (pin "1") (pinfunction "VDD_1") (pintype "passive"))
      (node (ref "GRB14") (pin "1") (pinfunction "VDD_1") (pintype "passive"))
      (node (ref "GRB15") (pin "1") (pinfunction "VDD_1") (pintype "passive"))
      (node (ref "GRB16") (pin "1") (pinfunction "VDD_1") (pintype "passive"))
      (node (ref "GRB17") (pin "1") (pinfunction "VDD_1") (pintype "passive"))
      (node (ref "GRB18") (pin "1") (pinfunction "VDD_1") (pintype "passive"))
      (node (ref "GRB19") (pin "1") (pinfunction "VDD_1") (pintype "passive"))
      (node (ref "GRB2") (pin "1") (pinfunction "VDD_1") (pintype "passive"))
      (node (ref "GRB20") (pin "1") (pinfunction "VDD_1") (pintype "passive"))
      (node (ref "GRB21") (pin "1") (pinfunction "VDD_1") (pintype "passive"))
      (node (ref "GRB22") (pin "1") (pinfunction "VDD_1") (pintype "passive"))
      (node (ref "GRB23") (pin "1") (pinfunction "VDD_1") (pintype "passive"))
      (node (ref "GRB24") (pin "1") (pinfunction "VDD_1") (pintype "passive"))
      (node (ref "GRB25") (pin "1") (pinfunction "VDD_1") (pintype "passive"))
      (node (ref "GRB26") (pin "1") (pinfunction "VDD_1") (pintype "passive"))
      (node (ref "GRB27") (pin "1") (pinfunction "VDD_1") (pintype "passive"))
      (node (ref "GRB3") (pin "1") (pinfunction "VDD_1") (pintype "passive"))
      (node (ref "GRB4") (pin "1") (pinfunction "VDD_1") (pintype "passive"))
      (node (ref "GRB5") (pin "1") (pinfunction "VDD_1") (pintype "passive"))
      (node (ref "GRB6") (pin "1") (pinfunction "VDD_1") (pintype "passive"))
      (node (ref "GRB7") (pin "1") (pinfunction "VDD_1") (pintype "passive"))
      (node (ref "GRB8") (pin "1") (pinfunction "VDD_1") (pintype "passive"))
      (node (ref "GRB9") (pin "1") (pinfunction "VDD_1") (pintype "passive"))
      (node (ref "L1") (pin "2") (pinfunction "2_2") (pintype "passive"))
      (node (ref "R10") (pin "2") (pinfunction "2_2") (pintype "passive"))
      (node (ref "R2") (pin "2") (pinfunction "2_2") (pintype "passive"))
      (node (ref "R8") (pin "2") (pinfunction "2_2") (pintype "passive"))
      (node (ref "U3") (pin "3") (pinfunction "I_3") (pintype "passive"))
      (node (ref "U4") (pin "10") (pinfunction "VDD_10") (pintype "passive"))
    )
    (net (code "64") (name "12V") (class "Default")
      (node (ref "E1") (pin "1") (pinfunction "A_1") (pintype "passive"))
      (node (ref "E7") (pin "1") (pinfunction "A_1") (pintype "passive"))
      (node (ref "JP1") (pin "5") (pinfunction "5_5") (pintype "passive"))
      (node (ref "R3") (pin "1") (pinfunction "1_1") (pintype "passive"))
      (node (ref "U2") (pin "5") (pinfunction "IN_5") (pintype "passive"))
      (node (ref "VD1") (pin "2") (pinfunction "K_2") (pintype "passive"))
    )
    (net (code "65") (name "ETX_12V") (class "Default")
      (node (ref "CON1") (pin "1") (pintype "power_in"))
      (node (ref "VD1") (pin "1") (pinfunction "A_1") (pintype "passive"))
    )
    (net (code "66") (name "GND") (class "Default")
      (node (ref "C1") (pin "1") (pinfunction "1_1") (pintype "passive"))
      (node (ref "C10") (pin "1") (pinfunction "1_1") (pintype "passive"))
      (node (ref "C11") (pin "1") (pinfunction "1_1") (pintype "passive"))
      (node (ref "C12") (pin "1") (pinfunction "1_1") (pintype "passive"))
      (node (ref "C13") (pin "1") (pinfunction "1_1") (pintype "passive"))
      (node (ref "C14") (pin "1") (pinfunction "1_1") (pintype "passive"))
      (node (ref "C15") (pin "1") (pinfunction "1_1") (pintype "passive"))
      (node (ref "C16") (pin "1") (pinfunction "1_1") (pintype "passive"))
      (node (ref "C17") (pin "1") (pinfunction "1_1") (pintype "passive"))
      (node (ref "C18") (pin "1") (pinfunction "1_1") (pintype "passive"))
      (node (ref "C19") (pin "1") (pinfunction "1_1") (pintype "passive"))
      (node (ref "C2") (pin "1") (pinfunction "1_1") (pintype "passive"))
      (node (ref "C20") (pin "1") (pinfunction "1_1") (pintype "passive"))
      (node (ref "C21") (pin "1") (pinfunction "1_1") (pintype "passive"))
      (node (ref "C22") (pin "1") (pinfunction "1_1") (pintype "passive"))
      (node (ref "C23") (pin "1") (pinfunction "1_1") (pintype "passive"))
      (node (ref "C24") (pin "1") (pinfunction "1_1") (pintype "passive"))
      (node (ref "C25") (pin "1") (pinfunction "1_1") (pintype "passive"))
      (node (ref "C26") (pin "1") (pinfunction "1_1") (pintype "passive"))
      (node (ref "C27") (pin "1") (pinfunction "1_1") (pintype "passive"))
      (node (ref "C28") (pin "1") (pinfunction "1_1") (pintype "passive"))
      (node (ref "C3") (pin "1") (pinfunction "1_1") (pintype "passive"))
      (node (ref "C30") (pin "1") (pinfunction "1_1") (pintype "passive"))
      (node (ref "C31") (pin "1") (pinfunction "1_1") (pintype "passive"))
      (node (ref "C32") (pin "1") (pinfunction "1_1") (pintype "passive"))
      (node (ref "C33") (pin "1") (pinfunction "1_1") (pintype "passive"))
      (node (ref "C34") (pin "1") (pinfunction "1_1") (pintype "passive"))
      (node (ref "C35") (pin "2") (pinfunction "2_2") (pintype "passive"))
      (node (ref "C36") (pin "2") (pinfunction "2_2") (pintype "passive"))
      (node (ref "C37") (pin "1") (pinfunction "1_1") (pintype "passive"))
      (node (ref "C38") (pin "1") (pinfunction "1_1") (pintype "passive"))
      (node (ref "C39") (pin "1") (pinfunction "1_1") (pintype "passive"))
      (node (ref "C40") (pin "1") (pinfunction "1_1") (pintype "passive"))
      (node (ref "C41") (pin "1") (pinfunction "1_1") (pintype "passive"))
      (node (ref "C42") (pin "1") (pinfunction "1_1") (pintype "passive"))
      (node (ref "C43") (pin "1") (pinfunction "1_1") (pintype "passive"))
      (node (ref "C44") (pin "1") (pinfunction "1_1") (pintype "passive"))
      (node (ref "C45") (pin "2") (pinfunction "2_2") (pintype "passive"))
      (node (ref "C46") (pin "2") (pinfunction "2_2") (pintype "passive"))
      (node (ref "C47") (pin "2") (pinfunction "2_2") (pintype "passive"))
      (node (ref "C48") (pin "1") (pinfunction "1_1") (pintype "passive"))
      (node (ref "C49") (pin "1") (pinfunction "1_1") (pintype "passive"))
      (node (ref "C5") (pin "1") (pinfunction "1_1") (pintype "passive"))
      (node (ref "C50") (pin "1") (pinfunction "1_1") (pintype "passive"))
      (node (ref "C51") (pin "1") (pinfunction "1_1") (pintype "passive"))
      (node (ref "C52") (pin "1") (pinfunction "1_1") (pintype "passive"))
      (node (ref "C53") (pin "1") (pinfunction "1_1") (pintype "passive"))
      (node (ref "C6") (pin "1") (pinfunction "1_1") (pintype "passive"))
      (node (ref "C7") (pin "1") (pinfunction "1_1") (pintype "passive"))
      (node (ref "C8") (pin "1") (pinfunction "1_1") (pintype "passive"))
      (node (ref "C9") (pin "1") (pinfunction "1_1") (pintype "passive"))
      (node (ref "CON1") (pin "2") (pintype "power_in"))
      (node (ref "E1") (pin "2") (pinfunction "K_2") (pintype "passive"))
      (node (ref "E2") (pin "2") (pinfunction "K_2") (pintype "passive"))
      (node (ref "E3") (pin "2") (pinfunction "K_2") (pintype "passive"))
      (node (ref "E4") (pin "2") (pinfunction "K_2") (pintype "passive"))
      (node (ref "E5") (pin "2") (pinfunction "K_2") (pintype "passive"))
      (node (ref "E6") (pin "2") (pinfunction "K_2") (pintype "passive"))
      (node (ref "E7") (pin "2") (pinfunction "K_2") (pintype "passive"))
      (node (ref "GRB1") (pin "3") (pinfunction "GND_3") (pintype "passive"))
      (node (ref "GRB10") (pin "3") (pinfunction "GND_3") (pintype "passive"))
      (node (ref "GRB11") (pin "3") (pinfunction "GND_3") (pintype "passive"))
      (node (ref "GRB12") (pin "3") (pinfunction "GND_3") (pintype "passive"))
      (node (ref "GRB13") (pin "3") (pinfunction "GND_3") (pintype "passive"))
      (node (ref "GRB14") (pin "3") (pinfunction "GND_3") (pintype "passive"))
      (node (ref "GRB15") (pin "3") (pinfunction "GND_3") (pintype "passive"))
      (node (ref "GRB16") (pin "3") (pinfunction "GND_3") (pintype "passive"))
      (node (ref "GRB17") (pin "3") (pinfunction "GND_3") (pintype "passive"))
      (node (ref "GRB18") (pin "3") (pinfunction "GND_3") (pintype "passive"))
      (node (ref "GRB19") (pin "3") (pinfunction "GND_3") (pintype "passive"))
      (node (ref "GRB2") (pin "3") (pinfunction "GND_3") (pintype "passive"))
      (node (ref "GRB20") (pin "3") (pinfunction "GND_3") (pintype "passive"))
      (node (ref "GRB21") (pin "3") (pinfunction "GND_3") (pintype "passive"))
      (node (ref "GRB22") (pin "3") (pinfunction "GND_3") (pintype "passive"))
      (node (ref "GRB23") (pin "3") (pinfunction "GND_3") (pintype "passive"))
      (node (ref "GRB24") (pin "3") (pinfunction "GND_3") (pintype "passive"))
      (node (ref "GRB25") (pin "3") (pinfunction "GND_3") (pintype "passive"))
      (node (ref "GRB26") (pin "3") (pinfunction "GND_3") (pintype "passive"))
      (node (ref "GRB27") (pin "3") (pinfunction "GND_3") (pintype "passive"))
      (node (ref "GRB3") (pin "3") (pinfunction "GND_3") (pintype "passive"))
      (node (ref "GRB4") (pin "3") (pinfunction "GND_3") (pintype "passive"))
      (node (ref "GRB5") (pin "3") (pinfunction "GND_3") (pintype "passive"))
      (node (ref "GRB6") (pin "3") (pinfunction "GND_3") (pintype "passive"))
      (node (ref "GRB7") (pin "3") (pinfunction "GND_3") (pintype "passive"))
      (node (ref "GRB8") (pin "3") (pinfunction "GND_3") (pintype "passive"))
      (node (ref "GRB9") (pin "3") (pinfunction "GND_3") (pintype "passive"))
      (node (ref "JP1") (pin "4") (pinfunction "4_4") (pintype "passive"))
      (node (ref "Q3") (pin "2") (pinfunction "e_2") (pintype "passive"))
      (node (ref "Q4") (pin "2") (pinfunction "e_2") (pintype "passive"))
      (node (ref "Q5") (pin "2") (pinfunction "e_2") (pintype "passive"))
      (node (ref "R22") (pin "1") (pinfunction "1_1") (pintype "passive"))
      (node (ref "R23") (pin "1") (pinfunction "1_1") (pintype "passive"))
      (node (ref "R24") (pin "1") (pinfunction "1_1") (pintype "passive"))
      (node (ref "R4") (pin "1") (pinfunction "1_1") (pintype "passive"))
      (node (ref "REC1") (pin "2") (pinfunction "GND_2") (pintype "passive"))
      (node (ref "REC2") (pin "2") (pinfunction "GND_2") (pintype "passive"))
      (node (ref "SWD1") (pin "2") (pinfunction "2_2") (pintype "passive"))
      (node (ref "U1") (pin "23") (pinfunction "VSS_23") (pintype "passive"))
      (node (ref "U1") (pin "44") (pinfunction "BOOT0_44") (pintype "passive"))
      (node (ref "U1") (pin "47") (pinfunction "VSS_47") (pintype "passive"))
      (node (ref "U1") (pin "8") (pinfunction "VSSA_8") (pintype "passive"))
      (node (ref "U2") (pin "2") (pinfunction "GND_2") (pintype "passive"))
      (node (ref "U3") (pin "1") (pinfunction "G_1") (pintype "passive"))
      (node (ref "U4") (pin "4") (pinfunction "GND_4") (pintype "passive"))
      (node (ref "U5") (pin "2") (pinfunction "GND_2") (pintype "passive"))
      (node (ref "U6") (pin "2") (pinfunction "GND_2") (pintype "passive"))
      (node (ref "U7") (pin "2") (pinfunction "GND_2") (pintype "passive"))
      (node (ref "UART") (pin "2") (pinfunction "2_2") (pintype "passive"))
    )
    (net (code "67") (name "Net-(D1-A)") (class "Default")
      (node (ref "D1") (pin "1") (pinfunction "A_1") (pintype "passive"))
      (node (ref "R13") (pin "2") (pinfunction "2_2") (pintype "passive"))
    )
    (net (code "68") (name "Net-(D1-K)") (class "Default")
      (node (ref "D1") (pin "2") (pinfunction "K_2") (pintype "passive"))
      (node (ref "Q4") (pin "3") (pinfunction "c_3") (pintype "passive"))
    )
    (net (code "69") (name "Net-(D2-A)") (class "Default")
      (node (ref "D2") (pin "1") (pinfunction "A_1") (pintype "passive"))
      (node (ref "R14") (pin "2") (pinfunction "2_2") (pintype "passive"))
    )
    (net (code "70") (name "Net-(D2-K)") (class "Default")
      (node (ref "D2") (pin "2") (pinfunction "K_2") (pintype "passive"))
      (node (ref "Q5") (pin "3") (pinfunction "c_3") (pintype "passive"))
    )
    (net (code "71") (name "Net-(Q1-G)") (class "Default")
      (node (ref "Q1") (pin "1") (pinfunction "G_1") (pintype "passive"))
      (node (ref "R5") (pin "1") (pinfunction "1_1") (pintype "passive"))
    )
    (net (code "72") (name "Net-(Q2-G)") (class "Default")
      (node (ref "Q2") (pin "1") (pinfunction "G_1") (pintype "passive"))
      (node (ref "R6") (pin "1") (pinfunction "1_1") (pintype "passive"))
    )
    (net (code "73") (name "Net-(Q3-b)") (class "Default")
      (node (ref "Q3") (pin "1") (pinfunction "b_1") (pintype "passive"))
      (node (ref "R19") (pin "2") (pinfunction "2_2") (pintype "passive"))
      (node (ref "R22") (pin "2") (pinfunction "2_2") (pintype "passive"))
    )
    (net (code "74") (name "Net-(Q3-c)") (class "Default")
      (node (ref "B1") (pin "2") (pinfunction "2_2") (pintype "passive"))
      (node (ref "Q3") (pin "3") (pinfunction "c_3") (pintype "passive"))
    )
    (net (code "75") (name "Net-(Q4-b)") (class "Default")
      (node (ref "Q4") (pin "1") (pinfunction "b_1") (pintype "passive"))
      (node (ref "R20") (pin "2") (pinfunction "2_2") (pintype "passive"))
      (node (ref "R23") (pin "2") (pinfunction "2_2") (pintype "passive"))
    )
    (net (code "76") (name "Net-(Q5-b)") (class "Default")
      (node (ref "Q5") (pin "1") (pinfunction "b_1") (pintype "passive"))
      (node (ref "R21") (pin "2") (pinfunction "2_2") (pintype "passive"))
      (node (ref "R24") (pin "2") (pinfunction "2_2") (pintype "passive"))
    )
    (net (code "77") (name "Net-(R25-Pad1)") (class "Default")
      (node (ref "R25") (pin "1") (pinfunction "1_1") (pintype "passive"))
      (node (ref "T1") (pin "1") (pintype "passive"))
    )
    (net (code "78") (name "Net-(R26-Pad1)") (class "Default")
      (node (ref "R26") (pin "1") (pinfunction "1_1") (pintype "passive"))
      (node (ref "T2") (pin "1") (pintype "passive"))
    )
    (net (code "79") (name "Net-(R27-Pad1)") (class "Default")
      (node (ref "R27") (pin "1") (pinfunction "1_1") (pintype "passive"))
      (node (ref "T3") (pin "1") (pintype "passive"))
    )
    (net (code "80") (name "Net-(REC1-OUT)") (class "Default")
      (node (ref "R11") (pin "1") (pinfunction "1_1") (pintype "passive"))
      (node (ref "R15") (pin "1") (pinfunction "1_1") (pintype "passive"))
      (node (ref "REC1") (pin "1") (pinfunction "OUT_1") (pintype "passive"))
    )
    (net (code "81") (name "Net-(REC1-VCC)") (class "Default")
      (node (ref "R17") (pin "1") (pinfunction "1_1") (pintype "passive"))
      (node (ref "REC1") (pin "3") (pinfunction "VCC_3") (pintype "passive"))
    )
    (net (code "82") (name "Net-(REC2-OUT)") (class "Default")
      (node (ref "R12") (pin "1") (pinfunction "1_1") (pintype "passive"))
      (node (ref "R16") (pin "1") (pinfunction "1_1") (pintype "passive"))
      (node (ref "REC2") (pin "1") (pinfunction "OUT_1") (pintype "passive"))
    )
    (net (code "83") (name "Net-(REC2-VCC)") (class "Default")
      (node (ref "R18") (pin "1") (pinfunction "1_1") (pintype "passive"))
      (node (ref "REC2") (pin "3") (pinfunction "VCC_3") (pintype "passive"))
    )
    (net (code "84") (name "Net-(U2-BS)") (class "Default")
      (node (ref "C4") (pin "1") (pinfunction "1_1") (pintype "passive"))
      (node (ref "U2") (pin "1") (pinfunction "BS_1") (pintype "passive"))
    )
    (net (code "85") (name "Net-(U2-EN)") (class "Default")
      (node (ref "R3") (pin "2") (pinfunction "2_2") (pintype "passive"))
      (node (ref "U2") (pin "4") (pinfunction "EN_4") (pintype "passive"))
    )
    (net (code "86") (name "Net-(U2-FB)") (class "Default")
      (node (ref "R2") (pin "1") (pinfunction "1_1") (pintype "passive"))
      (node (ref "R4") (pin "2") (pinfunction "2_2") (pintype "passive"))
      (node (ref "U2") (pin "3") (pinfunction "FB_3") (pintype "passive"))
    )
    (net (code "87") (name "Net-(U2-SW)") (class "Default")
      (node (ref "C4") (pin "2") (pinfunction "2_2") (pintype "passive"))
      (node (ref "L1") (pin "1") (pinfunction "1_1") (pintype "passive"))
      (node (ref "U2") (pin "6") (pinfunction "SW_6") (pintype "passive"))
    )
    (net (code "88") (name "Net-(U5-KEY)") (class "Default")
      (node (ref "R25") (pin "2") (pinfunction "2_2") (pintype "passive"))
      (node (ref "U5") (pin "3") (pinfunction "KEY_3") (pintype "passive"))
    )
    (net (code "89") (name "Net-(U5-TOG)") (class "Default")
      (node (ref "C45") (pin "1") (pinfunction "1_1") (pintype "passive"))
      (node (ref "U5") (pin "6") (pinfunction "TOG_6") (pintype "passive"))
    )
    (net (code "90") (name "Net-(U6-KEY)") (class "Default")
      (node (ref "R26") (pin "2") (pinfunction "2_2") (pintype "passive"))
      (node (ref "U6") (pin "3") (pinfunction "KEY_3") (pintype "passive"))
    )
    (net (code "91") (name "Net-(U6-TOG)") (class "Default")
      (node (ref "C46") (pin "1") (pinfunction "1_1") (pintype "passive"))
      (node (ref "U6") (pin "6") (pinfunction "TOG_6") (pintype "passive"))
    )
    (net (code "92") (name "Net-(U7-KEY)") (class "Default")
      (node (ref "R27") (pin "2") (pinfunction "2_2") (pintype "passive"))
      (node (ref "U7") (pin "3") (pinfunction "KEY_3") (pintype "passive"))
    )
    (net (code "93") (name "Net-(U7-TOG)") (class "Default")
      (node (ref "C47") (pin "1") (pinfunction "1_1") (pintype "passive"))
      (node (ref "U7") (pin "6") (pinfunction "TOG_6") (pintype "passive"))
    )
    (net (code "94") (name "unconnected-(CON1-Pad3)") (class "Default")
      (node (ref "CON1") (pin "3") (pintype "power_in+no_connect"))
    )
    (net (code "95") (name "unconnected-(GRB3-DOUT-Pad2)") (class "Default")
      (node (ref "GRB3") (pin "2") (pinfunction "DOUT_2") (pintype "passive"))
    )
    (net (code "96") (name "unconnected-(GRB27-DOUT-Pad2)") (class "Default")
      (node (ref "GRB27") (pin "2") (pinfunction "DOUT_2") (pintype "passive"))
    )
    (net (code "97") (name "unconnected-(U1A-PA0-Pad10)") (class "Default")
      (node (ref "U1") (pin "10") (pinfunction "PA0_10") (pintype "passive"))
    )
    (net (code "98") (name "unconnected-(U1A-PA1-Pad11)") (class "Default")
      (node (ref "U1") (pin "11") (pinfunction "PA1_11") (pintype "passive"))
    )
    (net (code "99") (name "unconnected-(U1A-PB0-Pad18)") (class "Default")
      (node (ref "U1") (pin "18") (pinfunction "PB0_18") (pintype "passive"))
    )
    (net (code "100") (name "unconnected-(U1A-PB1-Pad19)") (class "Default")
      (node (ref "U1") (pin "19") (pinfunction "PB1_19") (pintype "passive"))
    )
    (net (code "101") (name "unconnected-(U1A-PB2-Pad20)") (class "Default")
      (node (ref "U1") (pin "20") (pinfunction "PB2_20") (pintype "passive"))
    )
    (net (code "102") (name "unconnected-(U1A-PB4-Pad40)") (class "Default")
      (node (ref "U1") (pin "40") (pinfunction "PB4_40") (pintype "passive"))
    )
    (net (code "103") (name "unconnected-(U1A-PB5-Pad41)") (class "Default")
      (node (ref "U1") (pin "41") (pinfunction "PB5_41") (pintype "passive"))
    )
    (net (code "104") (name "unconnected-(U1A-PB6-Pad42)") (class "Default")
      (node (ref "U1") (pin "42") (pinfunction "PB6_42") (pintype "passive"))
    )
    (net (code "105") (name "unconnected-(U1A-PB7-Pad43)") (class "Default")
      (node (ref "U1") (pin "43") (pinfunction "PB7_43") (pintype "passive"))
    )
    (net (code "106") (name "unconnected-(U1A-PB10-Pad21)") (class "Default")
      (node (ref "U1") (pin "21") (pinfunction "PB10_21") (pintype "passive"))
    )
    (net (code "107") (name "unconnected-(U1A-PB11-Pad22)") (class "Default")
      (node (ref "U1") (pin "22") (pinfunction "PB11_22") (pintype "passive"))
    )
    (net (code "108") (name "unconnected-(U1A-PB13-Pad26)") (class "Default")
      (node (ref "U1") (pin "26") (pinfunction "PB13_26") (pintype "passive"))
    )
    (net (code "109") (name "unconnected-(U1A-PB15-Pad28)") (class "Default")
      (node (ref "U1") (pin "28") (pinfunction "PB15_28") (pintype "passive"))
    )
    (net (code "110") (name "unconnected-(U1A-PC13-Pad2)") (class "Default")
      (node (ref "U1") (pin "2") (pinfunction "PC13_2") (pintype "passive"))
    )
    (net (code "111") (name "unconnected-(U1A-PC14-OSC32_IN(PC14)-Pad3)") (class "Default")
      (node (ref "U1") (pin "3") (pinfunction "PC14-OSC32_IN(PC14)_3") (pintype "passive"))
    )
    (net (code "112") (name "unconnected-(U1A-PC15-OSC32_OUT(PC15)-Pad4)") (class "Default")
      (node (ref "U1") (pin "4") (pinfunction "PC15-OSC32_OUT(PC15)_4") (pintype "passive"))
    )
    (net (code "113") (name "unconnected-(U1A-PF6-Pad35)") (class "Default")
      (node (ref "U1") (pin "35") (pinfunction "PF6_35") (pintype "passive"))
    )
    (net (code "114") (name "unconnected-(U1A-PF7-Pad36)") (class "Default")
      (node (ref "U1") (pin "36") (pinfunction "PF7_36") (pintype "passive"))
    )
    (net (code "115") (name "unconnected-(U5-AHLB-Pad4)") (class "Default")
      (node (ref "U5") (pin "4") (pinfunction "AHLB_4") (pintype "passive"))
    )
    (net (code "116") (name "unconnected-(U6-AHLB-Pad4)") (class "Default")
      (node (ref "U6") (pin "4") (pinfunction "AHLB_4") (pintype "passive"))
    )
    (net (code "117") (name "unconnected-(U7-AHLB-Pad4)") (class "Default")
      (node (ref "U7") (pin "4") (pinfunction "AHLB_4") (pintype "passive"))
    )
  )
)
